# bpod_stepper_1_4_2.net
KiCad netlist of a schematic drawn in EAGLE
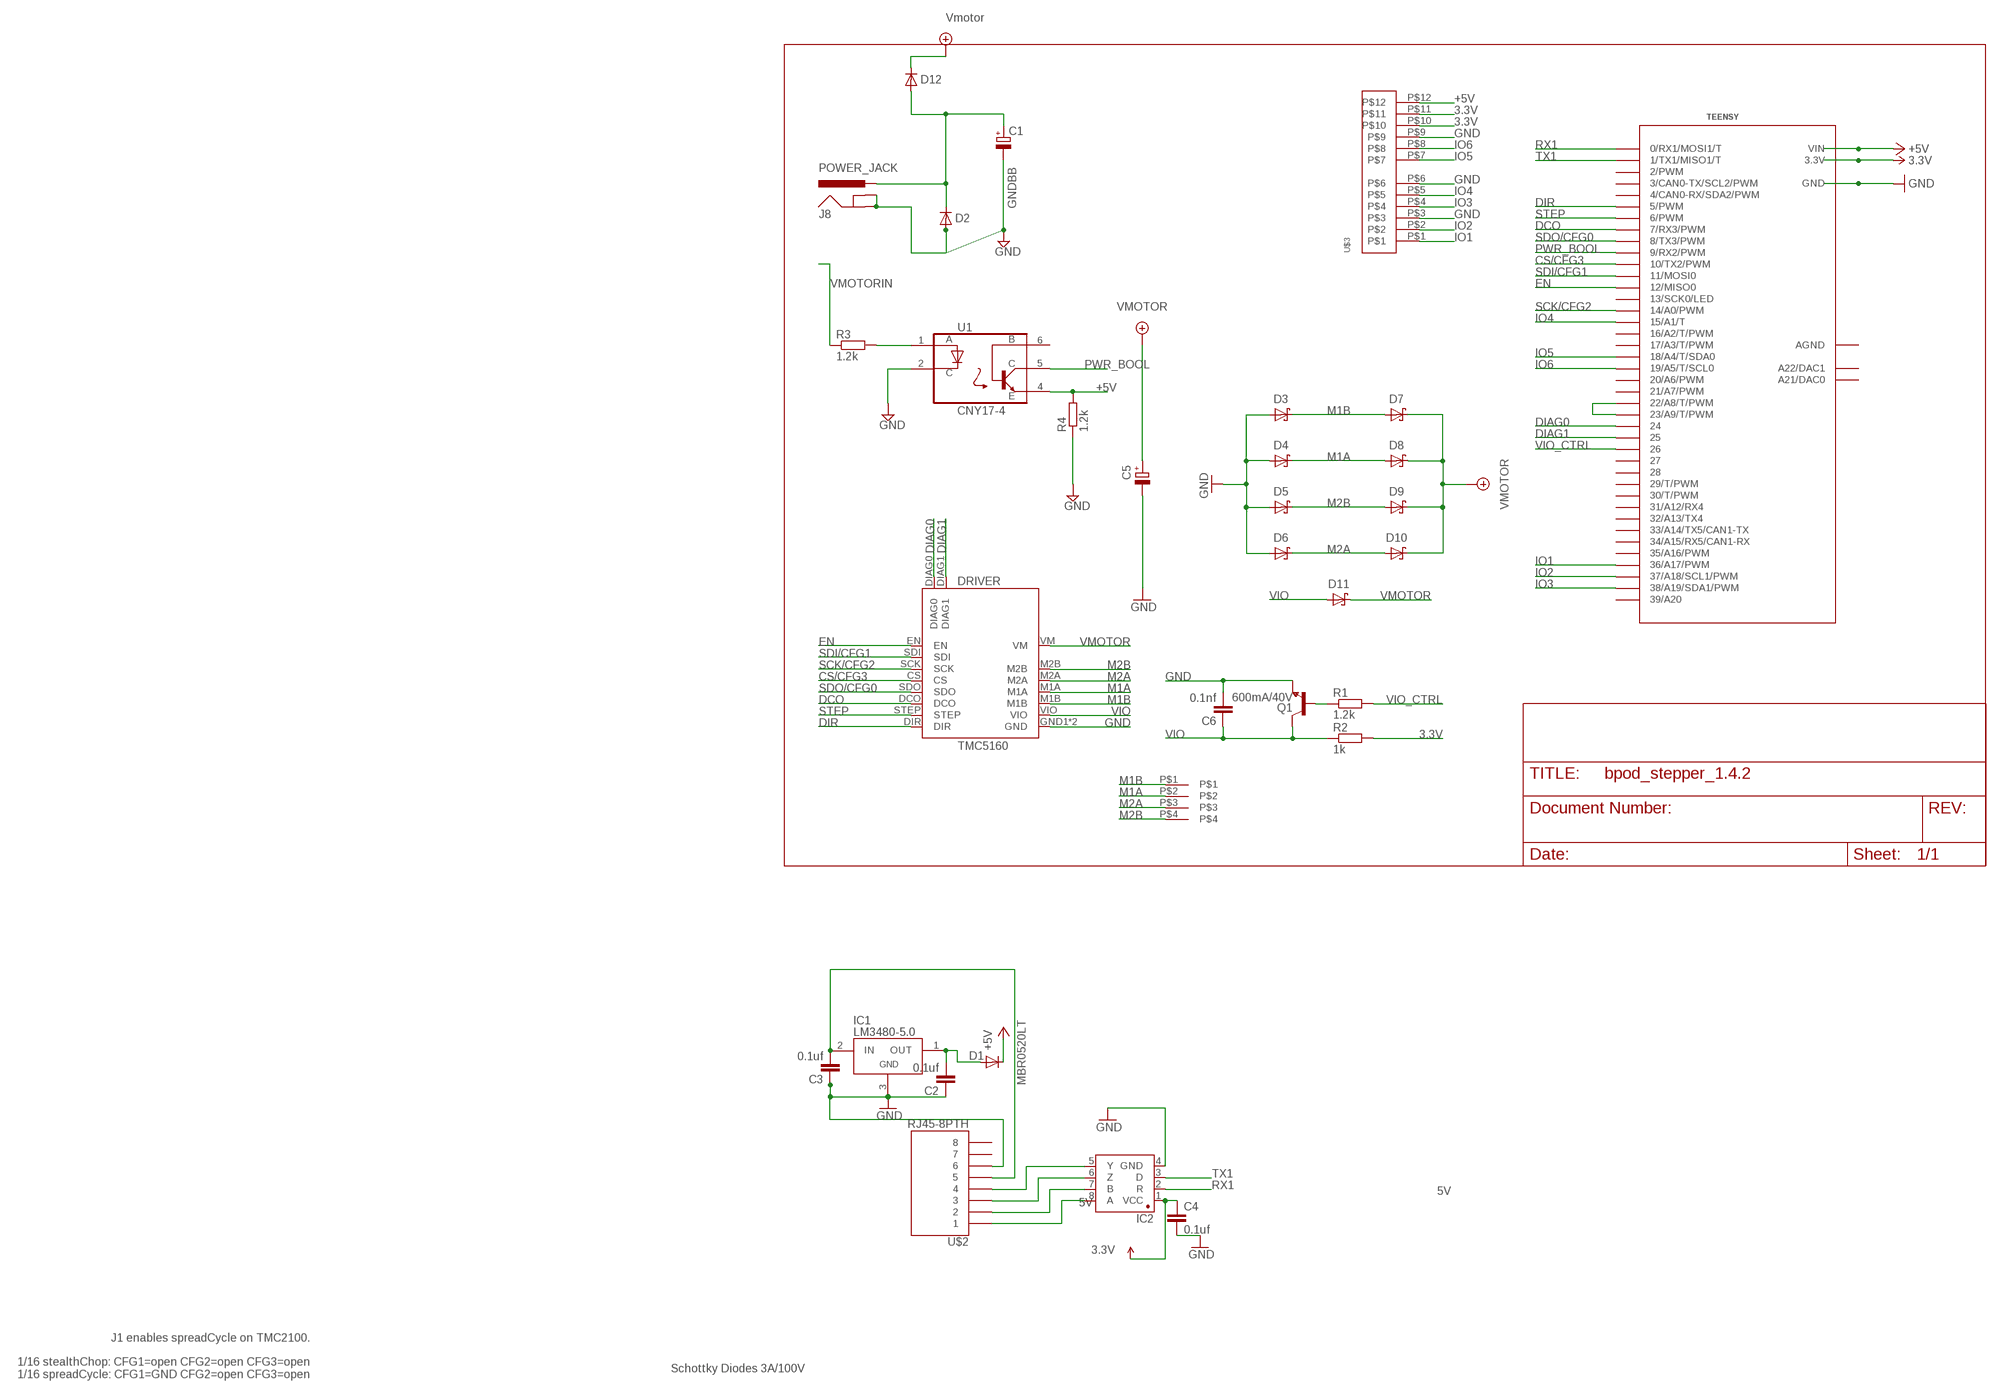
[diagram p0: schematic, sheet 1]

(export (version "E")
  (design (tool "Eeschema 10.0.6"))
  (components
    (comp (ref "C1")
      (value "CPOL-EUG")
      (footprint "eagle-import:PANASONIC_G")
      (libsource (lib "eagle-import") (part "CPOL-EUG"))
    )
    (comp (ref "C2")
      (value "0.1uf")
      (footprint "eagle-import:1206@1")
      (libsource (lib "eagle-import") (part "CAP1206"))
    )
    (comp (ref "C3")
      (value "0.1uf")
      (footprint "eagle-import:1206@1")
      (libsource (lib "eagle-import") (part "CAP1206"))
    )
    (comp (ref "C4")
      (value "0.1uf")
      (footprint "eagle-import:1206@1")
      (libsource (lib "eagle-import") (part "CAP1206"))
    )
    (comp (ref "C5")
      (value "CPOL-EUG")
      (footprint "eagle-import:PANASONIC_G")
      (libsource (lib "eagle-import") (part "CPOL-EUG"))
    )
    (comp (ref "C6")
      (value "0.1nf")
      (footprint "eagle-import:1206@1")
      (libsource (lib "eagle-import") (part "CAP1206"))
    )
    (comp (ref "D1")
      (value "MBR0520LT")
      (footprint "eagle-import:SOD123")
      (libsource (lib "eagle-import") (part "MBR0520LT"))
    )
    (comp (ref "D2")
      (value "DIODE-DO214AA")
      (footprint "eagle-import:DO214AA")
      (libsource (lib "eagle-import") (part "DIODE-DO214AA"))
    )
    (comp (ref "D3")
      (value "S310FA")
      (footprint "eagle-import:SOD123")
      (libsource (lib "eagle-import") (part "D_SCHOTTKY-SOD123"))
    )
    (comp (ref "D4")
      (value "S310FA")
      (footprint "eagle-import:SOD123")
      (libsource (lib "eagle-import") (part "D_SCHOTTKY-SOD123"))
    )
    (comp (ref "D5")
      (value "S310FA")
      (footprint "eagle-import:SOD123")
      (libsource (lib "eagle-import") (part "D_SCHOTTKY-SOD123"))
    )
    (comp (ref "D6")
      (value "S310FA")
      (footprint "eagle-import:SOD123")
      (libsource (lib "eagle-import") (part "D_SCHOTTKY-SOD123"))
    )
    (comp (ref "D7")
      (value "S310FA")
      (footprint "eagle-import:SOD123")
      (libsource (lib "eagle-import") (part "D_SCHOTTKY-SOD123"))
    )
    (comp (ref "D8")
      (value "S310FA")
      (footprint "eagle-import:SOD123")
      (libsource (lib "eagle-import") (part "D_SCHOTTKY-SOD123"))
    )
    (comp (ref "D9")
      (value "S310FA")
      (footprint "eagle-import:SOD123")
      (libsource (lib "eagle-import") (part "D_SCHOTTKY-SOD123"))
    )
    (comp (ref "D10")
      (value "S310FA")
      (footprint "eagle-import:SOD123")
      (libsource (lib "eagle-import") (part "D_SCHOTTKY-SOD123"))
    )
    (comp (ref "D11")
      (value "S310FA")
      (footprint "eagle-import:SOD123")
      (libsource (lib "eagle-import") (part "D_SCHOTTKY-SOD123"))
    )
    (comp (ref "D12")
      (value "DIODE-DO214AA")
      (footprint "eagle-import:DO214AA")
      (libsource (lib "eagle-import") (part "DIODE-DO214AA"))
    )
    (comp (ref "DRIVER")
      (value "TMC5160")
      (footprint "eagle-import:TMC5160")
      (libsource (lib "eagle-import") (part "TMC5160"))
    )
    (comp (ref "IC1")
      (value "LM3480-5.0")
      (footprint "eagle-import:SOT-23-3")
      (libsource (lib "eagle-import") (part "LM3480-5.0"))
    )
    (comp (ref "IC2")
      (value "SN65HVD31DR")
      (footprint "eagle-import:SO08")
      (libsource (lib "eagle-import") (part "SN65HVD31DR"))
    )
    (comp (ref "J8")
      (value "POWER_JACK")
      (footprint "eagle-import:POWER_JACK_PTH")
      (libsource (lib "eagle-import") (part "POWER_JACK"))
    )
    (comp (ref "Q1")
      (value "600mA/40V")
      (footprint "eagle-import:SOT23-3")
      (libsource (lib "eagle-import") (part "TRANS_NPN-MMBT2222AL"))
    )
    (comp (ref "R1")
      (value "1.2k")
      (footprint "eagle-import:R1206")
      (libsource (lib "eagle-import") (part "R-EU_R1206"))
    )
    (comp (ref "R2")
      (value "1k")
      (footprint "eagle-import:R1206")
      (libsource (lib "eagle-import") (part "R-EU_R1206"))
    )
    (comp (ref "R3")
      (value "1.2k")
      (footprint "eagle-import:R1206")
      (libsource (lib "eagle-import") (part "R-EU_R1206"))
    )
    (comp (ref "R4")
      (value "1.2k")
      (footprint "eagle-import:R1206")
      (libsource (lib "eagle-import") (part "R-EU_R1206"))
    )
    (comp (ref "TEENSY")
      (value "TEENSY_3.6_DIL")
      (footprint "eagle-import:TEENSY_3.6_DIL")
      (libsource (lib "eagle-import") (part "TEENSY_3.6_DIL"))
    )
    (comp (ref "U$2")
      (value "RJ45-8PTH")
      (footprint "eagle-import:RJ45-8")
      (libsource (lib "eagle-import") (part "RJ45-8PTH"))
    )
    (comp (ref "U$3")
      (value "12POS_MOLEX_SOCKET")
      (footprint "eagle-import:12POS_MOLEX_SOCKET")
      (libsource (lib "eagle-import") (part "12POS_MOLEX_SOCKET"))
    )
    (comp (ref "U$4")
      (value "MOLEX395221004")
      (footprint "eagle-import:MOLEX395221004")
      (libsource (lib "eagle-import") (part "MOLEX395221004"))
    )
    (comp (ref "U1")
      (value "CNY17-4")
      (footprint "eagle-import:DIP762W50P254L730H410Q6")
      (fields (field (name "MF") "Vishay Semiconductor"))
      (libsource (lib "eagle-import") (part "CNY17-4"))
    )
  )
  (nets
    (net (code "1") (name "+5V") (class "Default")
      (node (ref "D1") (pin "C") (pinfunction "C_C") (pintype "passive"))
      (node (ref "R4") (pin "2") (pinfunction "2_2") (pintype "passive"))
      (node (ref "TEENSY") (pin "VIN") (pinfunction "VIN_VIN") (pintype "power_in"))
      (node (ref "U$3") (pin "P$12") (pinfunction "P$12_P$12") (pintype "bidirectional"))
      (node (ref "U1") (pin "4") (pinfunction "E_4") (pintype "passive"))
    )
    (net (code "2") (name "/AGND") (class "Default")
      (node (ref "TEENSY") (pin "AGND") (pinfunction "AGND_AGND") (pintype "power_in"))
    )
    (net (code "3") (name "/CS{slash}CFG3") (class "Default")
      (node (ref "DRIVER") (pin "CS") (pinfunction "CS_CS") (pintype "passive"))
      (node (ref "TEENSY") (pin "10") (pinfunction "10/TX2/PWM_10") (pintype "bidirectional"))
    )
    (net (code "4") (name "/DCO") (class "Default")
      (node (ref "DRIVER") (pin "DCO") (pinfunction "DCO_DCO") (pintype "passive"))
      (node (ref "TEENSY") (pin "7") (pinfunction "7/RX3/PWM_7") (pintype "bidirectional"))
    )
    (net (code "5") (name "/DIAG0") (class "Default")
      (node (ref "DRIVER") (pin "DIAG0") (pinfunction "DIAG0_DIAG0") (pintype "passive"))
      (node (ref "TEENSY") (pin "24") (pinfunction "24_24") (pintype "bidirectional"))
    )
    (net (code "6") (name "/DIAG1") (class "Default")
      (node (ref "DRIVER") (pin "DIAG1") (pinfunction "DIAG1_DIAG1") (pintype "passive"))
      (node (ref "TEENSY") (pin "25") (pinfunction "25_25") (pintype "bidirectional"))
    )
    (net (code "7") (name "/DIR") (class "Default")
      (node (ref "DRIVER") (pin "DIR") (pinfunction "DIR_DIR") (pintype "input"))
      (node (ref "TEENSY") (pin "5") (pinfunction "5/PWM_5") (pintype "bidirectional"))
    )
    (net (code "8") (name "/EN") (class "Default")
      (node (ref "DRIVER") (pin "EN") (pinfunction "EN_EN") (pintype "passive"))
      (node (ref "TEENSY") (pin "12") (pinfunction "12/MISO0_12") (pintype "bidirectional"))
    )
    (net (code "9") (name "/IO1") (class "Default")
      (node (ref "TEENSY") (pin "36/A17") (pinfunction "36/A17/PWM_36/A17") (pintype "bidirectional"))
      (node (ref "U$3") (pin "P$1") (pinfunction "P$1_P$1") (pintype "bidirectional"))
    )
    (net (code "10") (name "/IO2") (class "Default")
      (node (ref "TEENSY") (pin "37/A18") (pinfunction "37/A18/SCL1/PWM_37/A18") (pintype "bidirectional"))
      (node (ref "U$3") (pin "P$2") (pinfunction "P$2_P$2") (pintype "bidirectional"))
    )
    (net (code "11") (name "/IO3") (class "Default")
      (node (ref "TEENSY") (pin "38/A19") (pinfunction "38/A19/SDA1/PWM_38/A19") (pintype "bidirectional"))
      (node (ref "U$3") (pin "P$4") (pinfunction "P$4_P$4") (pintype "bidirectional"))
    )
    (net (code "12") (name "/IO4") (class "Default")
      (node (ref "TEENSY") (pin "15/A1") (pinfunction "15/A1/T_15/A1") (pintype "bidirectional"))
      (node (ref "U$3") (pin "P$5") (pinfunction "P$5_P$5") (pintype "bidirectional"))
    )
    (net (code "13") (name "/IO5") (class "Default")
      (node (ref "TEENSY") (pin "18/A4") (pinfunction "18/A4/T/SDA0_18/A4") (pintype "bidirectional"))
      (node (ref "U$3") (pin "P$7") (pinfunction "P$7_P$7") (pintype "bidirectional"))
    )
    (net (code "14") (name "/IO6") (class "Default")
      (node (ref "TEENSY") (pin "19/A5") (pinfunction "19/A5/T/SCL0_19/A5") (pintype "bidirectional"))
      (node (ref "U$3") (pin "P$8") (pinfunction "P$8_P$8") (pintype "bidirectional"))
    )
    (net (code "15") (name "/M1A") (class "Default")
      (node (ref "D4") (pin "C") (pinfunction "C_C") (pintype "passive"))
      (node (ref "D8") (pin "A") (pinfunction "A_A") (pintype "passive"))
      (node (ref "DRIVER") (pin "M1A") (pinfunction "M1A_M1A") (pintype "output"))
      (node (ref "U$4") (pin "P$2") (pinfunction "P$2_P$2") (pintype "bidirectional"))
    )
    (net (code "16") (name "/M1B") (class "Default")
      (node (ref "D3") (pin "C") (pinfunction "C_C") (pintype "passive"))
      (node (ref "D7") (pin "A") (pinfunction "A_A") (pintype "passive"))
      (node (ref "DRIVER") (pin "M1B") (pinfunction "M1B_M1B") (pintype "output"))
      (node (ref "U$4") (pin "P$1") (pinfunction "P$1_P$1") (pintype "bidirectional"))
    )
    (net (code "17") (name "/M2A") (class "Default")
      (node (ref "D10") (pin "A") (pinfunction "A_A") (pintype "passive"))
      (node (ref "D6") (pin "C") (pinfunction "C_C") (pintype "passive"))
      (node (ref "DRIVER") (pin "M2A") (pinfunction "M2A_M2A") (pintype "output"))
      (node (ref "U$4") (pin "P$3") (pinfunction "P$3_P$3") (pintype "bidirectional"))
    )
    (net (code "18") (name "/M2B") (class "Default")
      (node (ref "D5") (pin "C") (pinfunction "C_C") (pintype "passive"))
      (node (ref "D9") (pin "A") (pinfunction "A_A") (pintype "passive"))
      (node (ref "DRIVER") (pin "M2B") (pinfunction "M2B_M2B") (pintype "output"))
      (node (ref "U$4") (pin "P$4") (pinfunction "P$4_P$4") (pintype "bidirectional"))
    )
    (net (code "19") (name "/PWR_BOOL") (class "Default")
      (node (ref "TEENSY") (pin "9") (pinfunction "9/RX2/PWM_9") (pintype "bidirectional"))
      (node (ref "U1") (pin "5") (pinfunction "C`_5") (pintype "passive"))
    )
    (net (code "20") (name "/RX1") (class "Default")
      (node (ref "IC2") (pin "2") (pinfunction "R_2") (pintype "bidirectional"))
      (node (ref "TEENSY") (pin "0") (pinfunction "0/RX1/MOSI1/T_0") (pintype "bidirectional"))
    )
    (net (code "21") (name "/SCK{slash}CFG2") (class "Default")
      (node (ref "DRIVER") (pin "SCK") (pinfunction "SCK_SCK") (pintype "passive"))
      (node (ref "TEENSY") (pin "14/A0") (pinfunction "14/A0/PWM_14/A0") (pintype "bidirectional"))
    )
    (net (code "22") (name "/SDI{slash}CFG1") (class "Default")
      (node (ref "DRIVER") (pin "SDI") (pinfunction "SDI_SDI") (pintype "passive"))
      (node (ref "TEENSY") (pin "11") (pinfunction "11/MOSI0_11") (pintype "bidirectional"))
    )
    (net (code "23") (name "/SDO{slash}CFG0") (class "Default")
      (node (ref "DRIVER") (pin "SDO") (pinfunction "SDO_SDO") (pintype "passive"))
      (node (ref "TEENSY") (pin "8") (pinfunction "8/TX3/PWM_8") (pintype "bidirectional"))
    )
    (net (code "24") (name "/STEP") (class "Default")
      (node (ref "DRIVER") (pin "STEP") (pinfunction "STEP_STEP") (pintype "input"))
      (node (ref "TEENSY") (pin "6") (pinfunction "6/PWM_6") (pintype "bidirectional"))
    )
    (net (code "25") (name "/TX1") (class "Default")
      (node (ref "IC2") (pin "3") (pinfunction "D_3") (pintype "bidirectional"))
      (node (ref "TEENSY") (pin "1") (pinfunction "1/TX1/MISO1/T_1") (pintype "bidirectional"))
    )
    (net (code "26") (name "/VIO") (class "Default")
      (node (ref "C6") (pin "1") (pinfunction "1_1") (pintype "passive"))
      (node (ref "D11") (pin "A") (pinfunction "A_A") (pintype "passive"))
      (node (ref "DRIVER") (pin "VIO") (pinfunction "VIO_VIO") (pintype "power_in"))
      (node (ref "Q1") (pin "3") (pinfunction "C_3") (pintype "passive"))
      (node (ref "R2") (pin "1") (pinfunction "1_1") (pintype "passive"))
    )
    (net (code "27") (name "/VIO_CTRL") (class "Default")
      (node (ref "R1") (pin "2") (pinfunction "2_2") (pintype "passive"))
      (node (ref "TEENSY") (pin "26") (pinfunction "26_26") (pintype "bidirectional"))
    )
    (net (code "28") (name "/VMOTORIN") (class "Default")
      (node (ref "C1") (pin "+") (pinfunction "+_+") (pintype "passive"))
      (node (ref "D12") (pin "A") (pinfunction "A_A") (pintype "passive"))
      (node (ref "D2") (pin "C") (pinfunction "C_C") (pintype "passive"))
      (node (ref "J8") (pin "PWR") (pinfunction "PWR_PWR") (pintype "bidirectional"))
      (node (ref "R3") (pin "1") (pinfunction "1_1") (pintype "passive"))
    )
    (net (code "29") (name "3.3V") (class "Default")
      (node (ref "C4") (pin "1") (pinfunction "1_1") (pintype "passive"))
      (node (ref "IC2") (pin "1") (pinfunction "VCC_1") (pintype "bidirectional"))
      (node (ref "R2") (pin "2") (pinfunction "2_2") (pintype "passive"))
      (node (ref "TEENSY") (pin "3.3V") (pinfunction "3.3V_3.3V") (pintype "power_in"))
      (node (ref "TEENSY") (pin "3.3V3") (pinfunction "3.3V_3.3V3") (pintype "power_in"))
      (node (ref "U$3") (pin "P$10") (pinfunction "P$10_P$10") (pintype "bidirectional"))
      (node (ref "U$3") (pin "P$11") (pinfunction "P$11_P$11") (pintype "bidirectional"))
    )
    (net (code "30") (name "GND") (class "Default")
      (node (ref "C1") (pin "-") (pinfunction "-_-") (pintype "passive"))
      (node (ref "C2") (pin "1") (pinfunction "1_1") (pintype "passive"))
      (node (ref "C3") (pin "1") (pinfunction "1_1") (pintype "passive"))
      (node (ref "C4") (pin "2") (pinfunction "2_2") (pintype "passive"))
      (node (ref "C5") (pin "-") (pinfunction "-_-") (pintype "passive"))
      (node (ref "C6") (pin "2") (pinfunction "2_2") (pintype "passive"))
      (node (ref "D2") (pin "A") (pinfunction "A_A") (pintype "passive"))
      (node (ref "D3") (pin "A") (pinfunction "A_A") (pintype "passive"))
      (node (ref "D4") (pin "A") (pinfunction "A_A") (pintype "passive"))
      (node (ref "D5") (pin "A") (pinfunction "A_A") (pintype "passive"))
      (node (ref "D6") (pin "A") (pinfunction "A_A") (pintype "passive"))
      (node (ref "DRIVER") (pin "GND1") (pinfunction "GND_GND1") (pintype "power_in"))
      (node (ref "DRIVER") (pin "GND2") (pinfunction "GND_GND2") (pintype "power_in"))
      (node (ref "IC1") (pin "3") (pinfunction "GND_3") (pintype "power_in"))
      (node (ref "IC2") (pin "4") (pinfunction "GND_4") (pintype "bidirectional"))
      (node (ref "J8") (pin "GND") (pinfunction "GND_GND") (pintype "bidirectional"))
      (node (ref "J8") (pin "GNDBREAK") (pinfunction "GNDBREAK_GNDBREAK") (pintype "bidirectional"))
      (node (ref "Q1") (pin "2") (pinfunction "E_2") (pintype "passive"))
      (node (ref "R4") (pin "1") (pinfunction "1_1") (pintype "passive"))
      (node (ref "TEENSY") (pin "GND") (pinfunction "GND_GND") (pintype "power_in"))
      (node (ref "TEENSY") (pin "GND1") (pinfunction "GND_GND1") (pintype "power_in"))
      (node (ref "U$2") (pin "6") (pinfunction "6_6") (pintype "bidirectional"))
      (node (ref "U$3") (pin "P$3") (pinfunction "P$3_P$3") (pintype "bidirectional"))
      (node (ref "U$3") (pin "P$6") (pinfunction "P$6_P$6") (pintype "bidirectional"))
      (node (ref "U$3") (pin "P$9") (pinfunction "P$9_P$9") (pintype "bidirectional"))
      (node (ref "U1") (pin "2") (pinfunction "C_2") (pintype "passive"))
    )
    (net (code "31") (name "Net-(IC1-IN)") (class "Default")
      (node (ref "C3") (pin "2") (pinfunction "2_2") (pintype "passive"))
      (node (ref "IC1") (pin "2") (pinfunction "IN_2") (pintype "power_in"))
      (node (ref "U$2") (pin "5") (pinfunction "5_5") (pintype "bidirectional"))
    )
    (net (code "32") (name "Net-(IC1-OUT)") (class "Default")
      (node (ref "C2") (pin "2") (pinfunction "2_2") (pintype "passive"))
      (node (ref "D1") (pin "A") (pinfunction "A_A") (pintype "passive"))
      (node (ref "IC1") (pin "1") (pinfunction "OUT_1") (pintype "power_in"))
    )
    (net (code "33") (name "Net-(IC2-A)") (class "Default")
      (node (ref "IC2") (pin "8") (pinfunction "A_8") (pintype "bidirectional"))
      (node (ref "U$2") (pin "1") (pinfunction "1_1") (pintype "bidirectional"))
    )
    (net (code "34") (name "Net-(IC2-B)") (class "Default")
      (node (ref "IC2") (pin "7") (pinfunction "B_7") (pintype "bidirectional"))
      (node (ref "U$2") (pin "2") (pinfunction "2_2") (pintype "bidirectional"))
    )
    (net (code "35") (name "Net-(IC2-Y)") (class "Default")
      (node (ref "IC2") (pin "5") (pinfunction "Y_5") (pintype "bidirectional"))
      (node (ref "U$2") (pin "4") (pinfunction "4_4") (pintype "bidirectional"))
    )
    (net (code "36") (name "Net-(IC2-Z)") (class "Default")
      (node (ref "IC2") (pin "6") (pinfunction "Z_6") (pintype "bidirectional"))
      (node (ref "U$2") (pin "3") (pinfunction "3_3") (pintype "bidirectional"))
    )
    (net (code "37") (name "Net-(Q1-B)") (class "Default")
      (node (ref "Q1") (pin "1") (pinfunction "B_1") (pintype "passive"))
      (node (ref "R1") (pin "1") (pinfunction "1_1") (pintype "passive"))
    )
    (net (code "38") (name "Net-(TEENSY-22{slash}A8{slash}T{slash}PWM)") (class "Default")
      (node (ref "TEENSY") (pin "22/A8") (pinfunction "22/A8/T/PWM_22/A8") (pintype "bidirectional"))
      (node (ref "TEENSY") (pin "23/A9") (pinfunction "23/A9/T/PWM_23/A9") (pintype "bidirectional"))
    )
    (net (code "39") (name "Net-(U1-A)") (class "Default")
      (node (ref "R3") (pin "2") (pinfunction "2_2") (pintype "passive"))
      (node (ref "U1") (pin "1") (pinfunction "A_1") (pintype "passive"))
    )
    (net (code "40") (name "Vmotor") (class "Default")
      (node (ref "C5") (pin "+") (pinfunction "+_+") (pintype "passive"))
      (node (ref "D10") (pin "C") (pinfunction "C_C") (pintype "passive"))
      (node (ref "D11") (pin "C") (pinfunction "C_C") (pintype "passive"))
      (node (ref "D12") (pin "C") (pinfunction "C_C") (pintype "passive"))
      (node (ref "D7") (pin "C") (pinfunction "C_C") (pintype "passive"))
      (node (ref "D8") (pin "C") (pinfunction "C_C") (pintype "passive"))
      (node (ref "D9") (pin "C") (pinfunction "C_C") (pintype "passive"))
      (node (ref "DRIVER") (pin "VM") (pinfunction "VM_VM") (pintype "power_in"))
    )
    (net (code "41") (name "unconnected-(TEENSY-2{slash}PWM-Pad2)") (class "Default")
      (node (ref "TEENSY") (pin "2") (pinfunction "2/PWM_2") (pintype "bidirectional"))
    )
    (net (code "42") (name "unconnected-(TEENSY-3{slash}CAN0-TX{slash}SCL2{slash}PWM-Pad3)") (class "Default")
      (node (ref "TEENSY") (pin "3") (pinfunction "3/CAN0-TX/SCL2/PWM_3") (pintype "bidirectional"))
    )
    (net (code "43") (name "unconnected-(TEENSY-4{slash}CAN0-RX{slash}SDA2{slash}PWM-Pad4)") (class "Default")
      (node (ref "TEENSY") (pin "4") (pinfunction "4/CAN0-RX/SDA2/PWM_4") (pintype "bidirectional"))
    )
    (net (code "44") (name "unconnected-(TEENSY-13{slash}SCK0{slash}LED-Pad13)") (class "Default")
      (node (ref "TEENSY") (pin "13") (pinfunction "13/SCK0/LED_13") (pintype "bidirectional"))
    )
    (net (code "45") (name "unconnected-(TEENSY-16{slash}A2{slash}T{slash}PWM-Pad16{slash}A2)") (class "Default")
      (node (ref "TEENSY") (pin "16/A2") (pinfunction "16/A2/T/PWM_16/A2") (pintype "bidirectional"))
    )
    (net (code "46") (name "unconnected-(TEENSY-17{slash}A3{slash}T{slash}PWM-Pad17{slash}A3)") (class "Default")
      (node (ref "TEENSY") (pin "17/A3") (pinfunction "17/A3/T/PWM_17/A3") (pintype "bidirectional"))
    )
    (net (code "47") (name "unconnected-(TEENSY-20{slash}A6{slash}PWM-Pad20{slash}A6)") (class "Default")
      (node (ref "TEENSY") (pin "20/A6") (pinfunction "20/A6/PWM_20/A6") (pintype "bidirectional"))
    )
    (net (code "48") (name "unconnected-(TEENSY-21{slash}A7{slash}PWM-Pad21{slash}A7)") (class "Default")
      (node (ref "TEENSY") (pin "21/A7") (pinfunction "21/A7/PWM_21/A7") (pintype "bidirectional"))
    )
    (net (code "49") (name "unconnected-(TEENSY-29{slash}T{slash}PWM-Pad29)") (class "Default")
      (node (ref "TEENSY") (pin "29") (pinfunction "29/T/PWM_29") (pintype "bidirectional"))
    )
    (net (code "50") (name "unconnected-(TEENSY-30{slash}T{slash}PWM-Pad30)") (class "Default")
      (node (ref "TEENSY") (pin "30") (pinfunction "30/T/PWM_30") (pintype "bidirectional"))
    )
    (net (code "51") (name "unconnected-(TEENSY-31{slash}A12{slash}RX4-Pad31{slash}A12)") (class "Default")
      (node (ref "TEENSY") (pin "31/A12") (pinfunction "31/A12/RX4_31/A12") (pintype "bidirectional"))
    )
    (net (code "52") (name "unconnected-(TEENSY-32{slash}A13{slash}TX4-Pad32{slash}A13)") (class "Default")
      (node (ref "TEENSY") (pin "32/A13") (pinfunction "32/A13/TX4_32/A13") (pintype "bidirectional"))
    )
    (net (code "53") (name "unconnected-(TEENSY-33{slash}A14{slash}TX5{slash}CAN1-TX-Pad33{slash}A14)") (class "Default")
      (node (ref "TEENSY") (pin "33/A14") (pinfunction "33/A14/TX5/CAN1-TX_33/A14") (pintype "bidirectional"))
    )
    (net (code "54") (name "unconnected-(TEENSY-34{slash}A15{slash}RX5{slash}CAN1-RX-Pad34{slash}A15)") (class "Default")
      (node (ref "TEENSY") (pin "34/A15") (pinfunction "34/A15/RX5/CAN1-RX_34/A15") (pintype "bidirectional"))
    )
    (net (code "55") (name "unconnected-(TEENSY-35{slash}A16{slash}PWM-Pad35{slash}A16)") (class "Default")
      (node (ref "TEENSY") (pin "35/A16") (pinfunction "35/A16/PWM_35/A16") (pintype "bidirectional"))
    )
    (net (code "56") (name "unconnected-(TEENSY-A21{slash}DAC0-PadA21)") (class "Default")
      (node (ref "TEENSY") (pin "A21") (pinfunction "A21/DAC0_A21") (pintype "bidirectional"))
    )
    (net (code "57") (name "unconnected-(TEENSY-A22{slash}DAC1-PadA22)") (class "Default")
      (node (ref "TEENSY") (pin "A22") (pinfunction "A22/DAC1_A22") (pintype "bidirectional"))
    )
    (net (code "58") (name "unconnected-(TEENSY-Pad27)") (class "Default")
      (node (ref "TEENSY") (pin "27") (pinfunction "27_27") (pintype "bidirectional"))
    )
    (net (code "59") (name "unconnected-(TEENSY-Pad28)") (class "Default")
      (node (ref "TEENSY") (pin "28") (pinfunction "28_28") (pintype "bidirectional"))
    )
    (net (code "60") (name "unconnected-(TEENSY-Pad39{slash}A20)") (class "Default")
      (node (ref "TEENSY") (pin "39/A20") (pinfunction "39/A20_39/A20") (pintype "bidirectional"))
    )
    (net (code "61") (name "unconnected-(U$2-Pad7)") (class "Default")
      (node (ref "U$2") (pin "7") (pinfunction "7_7") (pintype "bidirectional"))
    )
    (net (code "62") (name "unconnected-(U$2-Pad8)") (class "Default")
      (node (ref "U$2") (pin "8") (pinfunction "8_8") (pintype "bidirectional"))
    )
    (net (code "63") (name "unconnected-(U1-B-Pad6)") (class "Default")
      (node (ref "U1") (pin "6") (pinfunction "B_6") (pintype "passive"))
    )
  )
)
